# Interfaces.net
KiCad netlist of a schematic drawn in Altium Designer
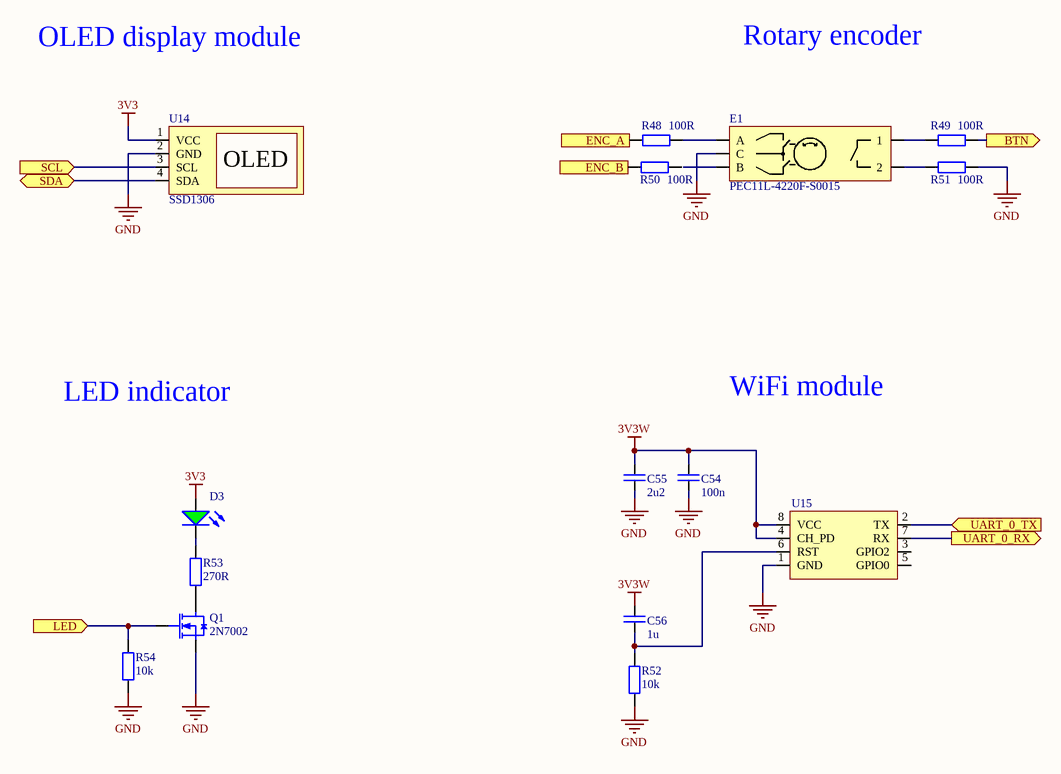
[diagram p0: Interfaces.SchDoc]

(export (version "E")
  (design (tool "Eeschema 10.0.6"))
  (components
    (comp (ref "C54")
      (value "100n")
      (footprint "C_0603")
      (description "Generic capacitor")
      (libsource (lib "DAQ_REV_B") (part "Capacitor"))
    )
    (comp (ref "C55")
      (value "2u2")
      (footprint "C_0603")
      (description "Generic capacitor")
      (libsource (lib "DAQ_REV_B") (part "Capacitor"))
    )
    (comp (ref "C56")
      (value "1u")
      (footprint "C_0603")
      (description "Generic capacitor")
      (libsource (lib "DAQ_REV_B") (part "Capacitor"))
    )
    (comp (ref "D3")
      (value "LED Green")
      (footprint "LED_0603")
      (description "Generic LED Green")
      (libsource (lib "DAQ_REV_B") (part "LED Green"))
    )
    (comp (ref "E1")
      (value "PEC11L-4220F-S0015")
      (description "Low Profile Encoder 15 PPR 2 Bit Quadrature 5VDC at 10 mA IP40 PCB Mount")
      (fields (field (name "PART NUMBER") "XRE0000") (field (name "MANUFACTURER") "BOURNS"))
      (libsource (lib "DAQ_REV_B") (part "PEC11L-4220F-S0015"))
    )
    (comp (ref "Q1")
      (value "2N7002")
      (footprint "SOT23-3")
      (description "60V 0.3A N-channel MOSFET")
      (fields (field (name "PART NUMBER") "XMN0002") (field (name "MANUFACTURER") "NXP"))
      (libsource (lib "DAQ_REV_B") (part "2N7002"))
    )
    (comp (ref "R48")
      (value "100R")
      (footprint "R_0603")
      (description "Generic resistor")
      (libsource (lib "DAQ_REV_B") (part "Resistor"))
    )
    (comp (ref "R49")
      (value "100R")
      (footprint "R_0603")
      (description "Generic resistor")
      (libsource (lib "DAQ_REV_B") (part "Resistor"))
    )
    (comp (ref "R50")
      (value "100R")
      (footprint "R_0603")
      (description "Generic resistor")
      (libsource (lib "DAQ_REV_B") (part "Resistor"))
    )
    (comp (ref "R51")
      (value "100R")
      (footprint "R_0603")
      (description "Generic resistor")
      (libsource (lib "DAQ_REV_B") (part "Resistor"))
    )
    (comp (ref "R52")
      (value "10k")
      (footprint "R_0603")
      (description "Generic resistor")
      (libsource (lib "DAQ_REV_B") (part "Resistor"))
    )
    (comp (ref "R53")
      (value "270R")
      (footprint "R_0603")
      (description "Generic resistor")
      (libsource (lib "DAQ_REV_B") (part "Resistor"))
    )
    (comp (ref "R54")
      (value "10k")
      (footprint "R_0603")
      (description "Generic resistor")
      (libsource (lib "DAQ_REV_B") (part "Resistor"))
    )
    (comp (ref "U14")
      (value "SSD1306")
      (footprint "OLED1")
      (description "Oled display module")
      (fields (field (name "PART NUMBER") "OLM0000"))
      (libsource (lib "DAQ_REV_B") (part "OLED_SSD1306"))
    )
    (comp (ref "U15")
      (value "ESP-01")
      (footprint "ESP-01")
      (description "WIFI module")
      (fields (field (name "PART NUMBER") "XWM0000"))
      (libsource (lib "DAQ_REV_B") (part "ESP-01"))
    )
  )
  (nets
    (net (code "1") (name "/BTN") (class "Default") (node (ref "R49") (pin "2") (pintype "passive")))
    (net (code "2") (name "/ENC_A") (class "Default") (node (ref "R48") (pin "1") (pintype "passive")))
    (net (code "3") (name "/ENC_B") (class "Default") (node (ref "R50") (pin "1") (pintype "passive")))
    (net (code "4") (name "/LED") (class "Default")
      (node (ref "Q1") (pin "1") (pinfunction "G_1") (pintype "passive"))
      (node (ref "R54") (pin "2") (pintype "passive"))
    )
    (net (code "5") (name "/SCL") (class "Default")
      (node (ref "U14") (pin "3") (pinfunction "SCL_3") (pintype "passive"))
    )
    (net (code "6") (name "/SDA") (class "Default")
      (node (ref "U14") (pin "4") (pinfunction "SDA_4") (pintype "passive"))
    )
    (net (code "7") (name "/UART_0_RX") (class "Default")
      (node (ref "U15") (pin "7") (pinfunction "RX_7") (pintype "passive"))
    )
    (net (code "8") (name "/UART_0_TX") (class "Default")
      (node (ref "U15") (pin "2") (pinfunction "TX_2") (pintype "passive"))
    )
    (net (code "9") (name "3V3") (class "Default")
      (node (ref "D3") (pin "2") (pinfunction "+_2") (pintype "passive"))
      (node (ref "U14") (pin "1") (pinfunction "VCC_1") (pintype "passive"))
    )
    (net (code "10") (name "3V3W") (class "Default")
      (node (ref "C54") (pin "2") (pinfunction "2_2") (pintype "passive"))
      (node (ref "C55") (pin "2") (pinfunction "2_2") (pintype "passive"))
      (node (ref "C56") (pin "2") (pinfunction "2_2") (pintype "passive"))
      (node (ref "U15") (pin "4") (pinfunction "CH_PD_4") (pintype "passive"))
      (node (ref "U15") (pin "8") (pinfunction "VCC_8") (pintype "passive"))
    )
    (net (code "11") (name "GND") (class "Default")
      (node (ref "C54") (pin "1") (pinfunction "1_1") (pintype "passive"))
      (node (ref "C55") (pin "1") (pinfunction "1_1") (pintype "passive"))
      (node (ref "E1") (pin "C") (pinfunction "C_C") (pintype "passive"))
      (node (ref "Q1") (pin "2") (pinfunction "S_2") (pintype "passive"))
      (node (ref "R51") (pin "2") (pintype "passive"))
      (node (ref "R52") (pin "1") (pintype "passive"))
      (node (ref "R54") (pin "1") (pintype "passive"))
      (node (ref "U14") (pin "2") (pinfunction "GND_2") (pintype "passive"))
      (node (ref "U15") (pin "1") (pinfunction "GND_1") (pintype "passive"))
    )
    (net (code "12") (name "Net-(D3--)") (class "Default")
      (node (ref "D3") (pin "1") (pinfunction "-_1") (pintype "passive"))
      (node (ref "R53") (pin "2") (pintype "passive"))
    )
    (net (code "13") (name "Net-(E1-Pad1)") (class "Default")
      (node (ref "E1") (pin "1") (pinfunction "1_1") (pintype "passive"))
      (node (ref "R49") (pin "1") (pintype "passive"))
    )
    (net (code "14") (name "Net-(E1-Pad2)") (class "Default")
      (node (ref "E1") (pin "2") (pinfunction "2_2") (pintype "passive"))
      (node (ref "R51") (pin "1") (pintype "passive"))
    )
    (net (code "15") (name "Net-(E1-PadA)") (class "Default")
      (node (ref "E1") (pin "A") (pinfunction "A_A") (pintype "passive"))
      (node (ref "R48") (pin "2") (pintype "passive"))
    )
    (net (code "16") (name "Net-(Q1-D)") (class "Default")
      (node (ref "Q1") (pin "3") (pinfunction "D_3") (pintype "passive"))
      (node (ref "R53") (pin "1") (pintype "passive"))
    )
    (net (code "17") (name "Net-(U15-RST)") (class "Default")
      (node (ref "C56") (pin "1") (pinfunction "1_1") (pintype "passive"))
      (node (ref "R52") (pin "2") (pintype "passive"))
      (node (ref "U15") (pin "6") (pinfunction "RST_6") (pintype "passive"))
    )
    (net (code "18") (name "unconnected-(E1-PadB)") (class "Default")
      (node (ref "E1") (pin "B") (pinfunction "B_B") (pintype "passive"))
    )
    (net (code "19") (name "unconnected-(R50-Pad2)") (class "Default")
      (node (ref "R50") (pin "2") (pintype "passive"))
    )
    (net (code "20") (name "unconnected-(U15-GPIO0-Pad5)") (class "Default")
      (node (ref "U15") (pin "5") (pinfunction "GPIO0_5") (pintype "passive"))
    )
    (net (code "21") (name "unconnected-(U15-GPIO2-Pad3)") (class "Default")
      (node (ref "U15") (pin "3") (pinfunction "GPIO2_3") (pintype "passive"))
    )
  )
)
